# DigitalSensors.net
KiCad netlist of a schematic drawn in Altium Designer
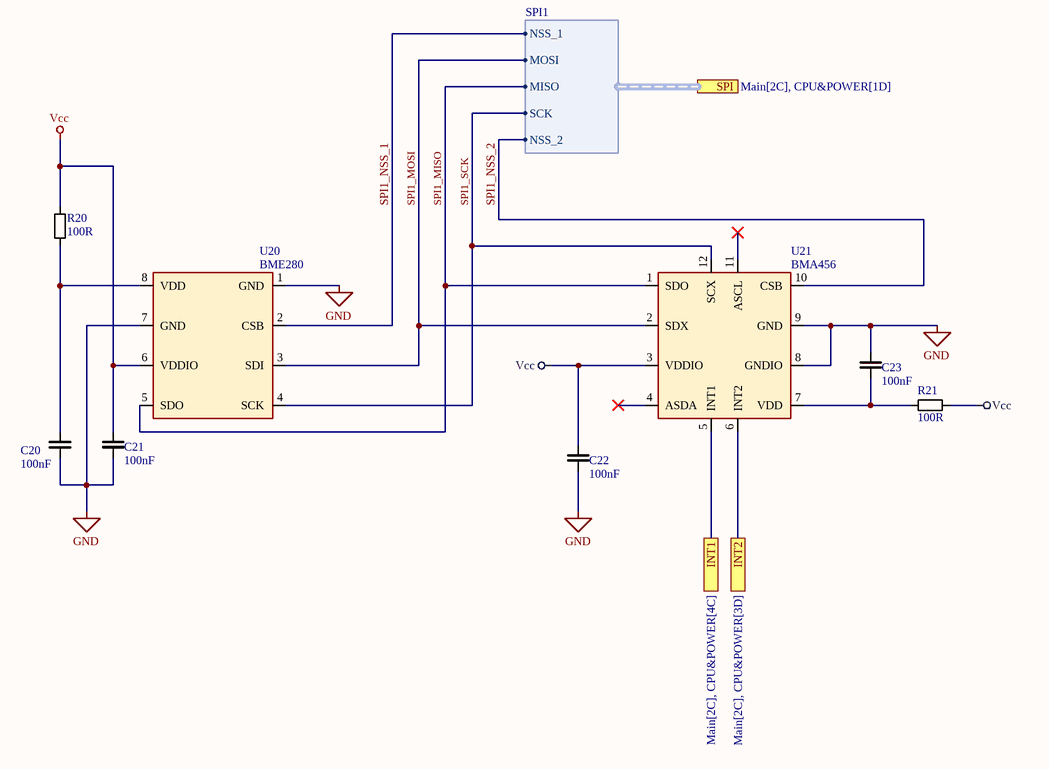
[diagram p0: DigitalSensors.SchDoc]

(export (version "E")
  (design (tool "Eeschema 10.0.6"))
  (components
    (comp (ref "C20")
      (value "100nF")
      (footprint "0402_CAP")
      (description "Ceramic capacitor")
      (libsource (lib "Cap") (part "Cap"))
    )
    (comp (ref "C21")
      (value "100nF")
      (footprint "0402_CAP")
      (description "Ceramic capacitor")
      (libsource (lib "Cap") (part "Cap"))
    )
    (comp (ref "C22")
      (value "100nF")
      (footprint "0402_CAP")
      (description "Ceramic capacitor")
      (libsource (lib "Cap") (part "Cap"))
    )
    (comp (ref "C23")
      (value "100nF")
      (footprint "0402_CAP")
      (description "Ceramic capacitor")
      (libsource (lib "Cap") (part "Cap"))
    )
    (comp (ref "R20")
      (value "100R")
      (footprint "0402_RES")
      (description "Resistor")
      (libsource (lib "RES") (part "RES"))
    )
    (comp (ref "R21")
      (value "100R")
      (footprint "0402_RES")
      (description "Resistor")
      (libsource (lib "RES") (part "RES"))
    )
    (comp (ref "U20") (value "BME280") (footprint "MODBME280_m") (libsource (lib "SchemLib") (part "BME280")))
    (comp (ref "U21")
      (value "BMA456")
      (footprint "BOSCH_LGA-12")
      (libsource (lib "SchemLib") (part "BMA456"))
    )
  )
  (nets
    (net (code "2") (name "/INT1") (class "Default")
      (node (ref "U21") (pin "5") (pinfunction "INT1_5") (pintype "passive"))
    )
    (net (code "3") (name "/INT2") (class "Default")
      (node (ref "U21") (pin "6") (pinfunction "INT2_6") (pintype "passive"))
    )
    (net (code "4") (name "/SPI1_MISO") (class "Default")
      (node (ref "U20") (pin "5") (pinfunction "SDO_5") (pintype "passive"))
      (node (ref "U21") (pin "1") (pinfunction "SDO_1") (pintype "passive"))
    )
    (net (code "5") (name "/SPI1_MOSI") (class "Default")
      (node (ref "U20") (pin "3") (pinfunction "SDI_3") (pintype "passive"))
      (node (ref "U21") (pin "2") (pinfunction "SDX_2") (pintype "passive"))
    )
    (net (code "6") (name "/SPI1_NSS_1") (class "Default")
      (node (ref "U20") (pin "2") (pinfunction "CSB_2") (pintype "passive"))
    )
    (net (code "7") (name "/SPI1_NSS_2") (class "Default")
      (node (ref "U21") (pin "10") (pinfunction "CSB_10") (pintype "passive"))
    )
    (net (code "8") (name "/SPI1_SCK") (class "Default")
      (node (ref "U20") (pin "4") (pinfunction "SCK_4") (pintype "passive"))
      (node (ref "U21") (pin "12") (pinfunction "SCX_12") (pintype "passive"))
    )
    (net (code "10") (name "GND") (class "Default")
      (node (ref "C20") (pin "1") (pinfunction "1_1") (pintype "passive"))
      (node (ref "C21") (pin "1") (pinfunction "1_1") (pintype "passive"))
      (node (ref "C22") (pin "1") (pinfunction "1_1") (pintype "passive"))
      (node (ref "C23") (pin "2") (pinfunction "2_2") (pintype "passive"))
      (node (ref "U20") (pin "1") (pinfunction "GND_1") (pintype "passive"))
      (node (ref "U20") (pin "7") (pinfunction "GND_7") (pintype "passive"))
      (node (ref "U21") (pin "8") (pinfunction "GNDIO_8") (pintype "passive"))
      (node (ref "U21") (pin "9") (pinfunction "GND_9") (pintype "passive"))
    )
    (net (code "11") (name "Net-(U20-VDD)") (class "Default")
      (node (ref "C20") (pin "2") (pinfunction "2_2") (pintype "passive"))
      (node (ref "R20") (pin "1") (pinfunction "1_1") (pintype "passive"))
      (node (ref "U20") (pin "8") (pinfunction "VDD_8") (pintype "passive"))
    )
    (net (code "12") (name "Net-(U21-VDD)") (class "Default")
      (node (ref "C23") (pin "1") (pinfunction "1_1") (pintype "passive"))
      (node (ref "R21") (pin "1") (pinfunction "1_1") (pintype "passive"))
      (node (ref "U21") (pin "7") (pinfunction "VDD_7") (pintype "passive"))
    )
    (net (code "13") (name "Vcc") (class "Default")
      (node (ref "C21") (pin "2") (pinfunction "2_2") (pintype "passive"))
      (node (ref "C22") (pin "2") (pinfunction "2_2") (pintype "passive"))
      (node (ref "R20") (pin "2") (pinfunction "2_2") (pintype "passive"))
      (node (ref "R21") (pin "2") (pinfunction "2_2") (pintype "passive"))
      (node (ref "U20") (pin "6") (pinfunction "VDDIO_6") (pintype "passive"))
      (node (ref "U21") (pin "3") (pinfunction "VDDIO_3") (pintype "passive"))
    )
    (net (code "14") (name "unconnected-(U21-ASCL-Pad11)") (class "Default")
      (node (ref "U21") (pin "11") (pinfunction "ASCL_11") (pintype "passive+no_connect"))
    )
    (net (code "15") (name "unconnected-(U21-ASDA-Pad4)") (class "Default")
      (node (ref "U21") (pin "4") (pinfunction "ASDA_4") (pintype "passive+no_connect"))
    )
  )
)
